# xt60_gh1_25.net
KiCad netlist of a schematic drawn in EasyEDA Pro
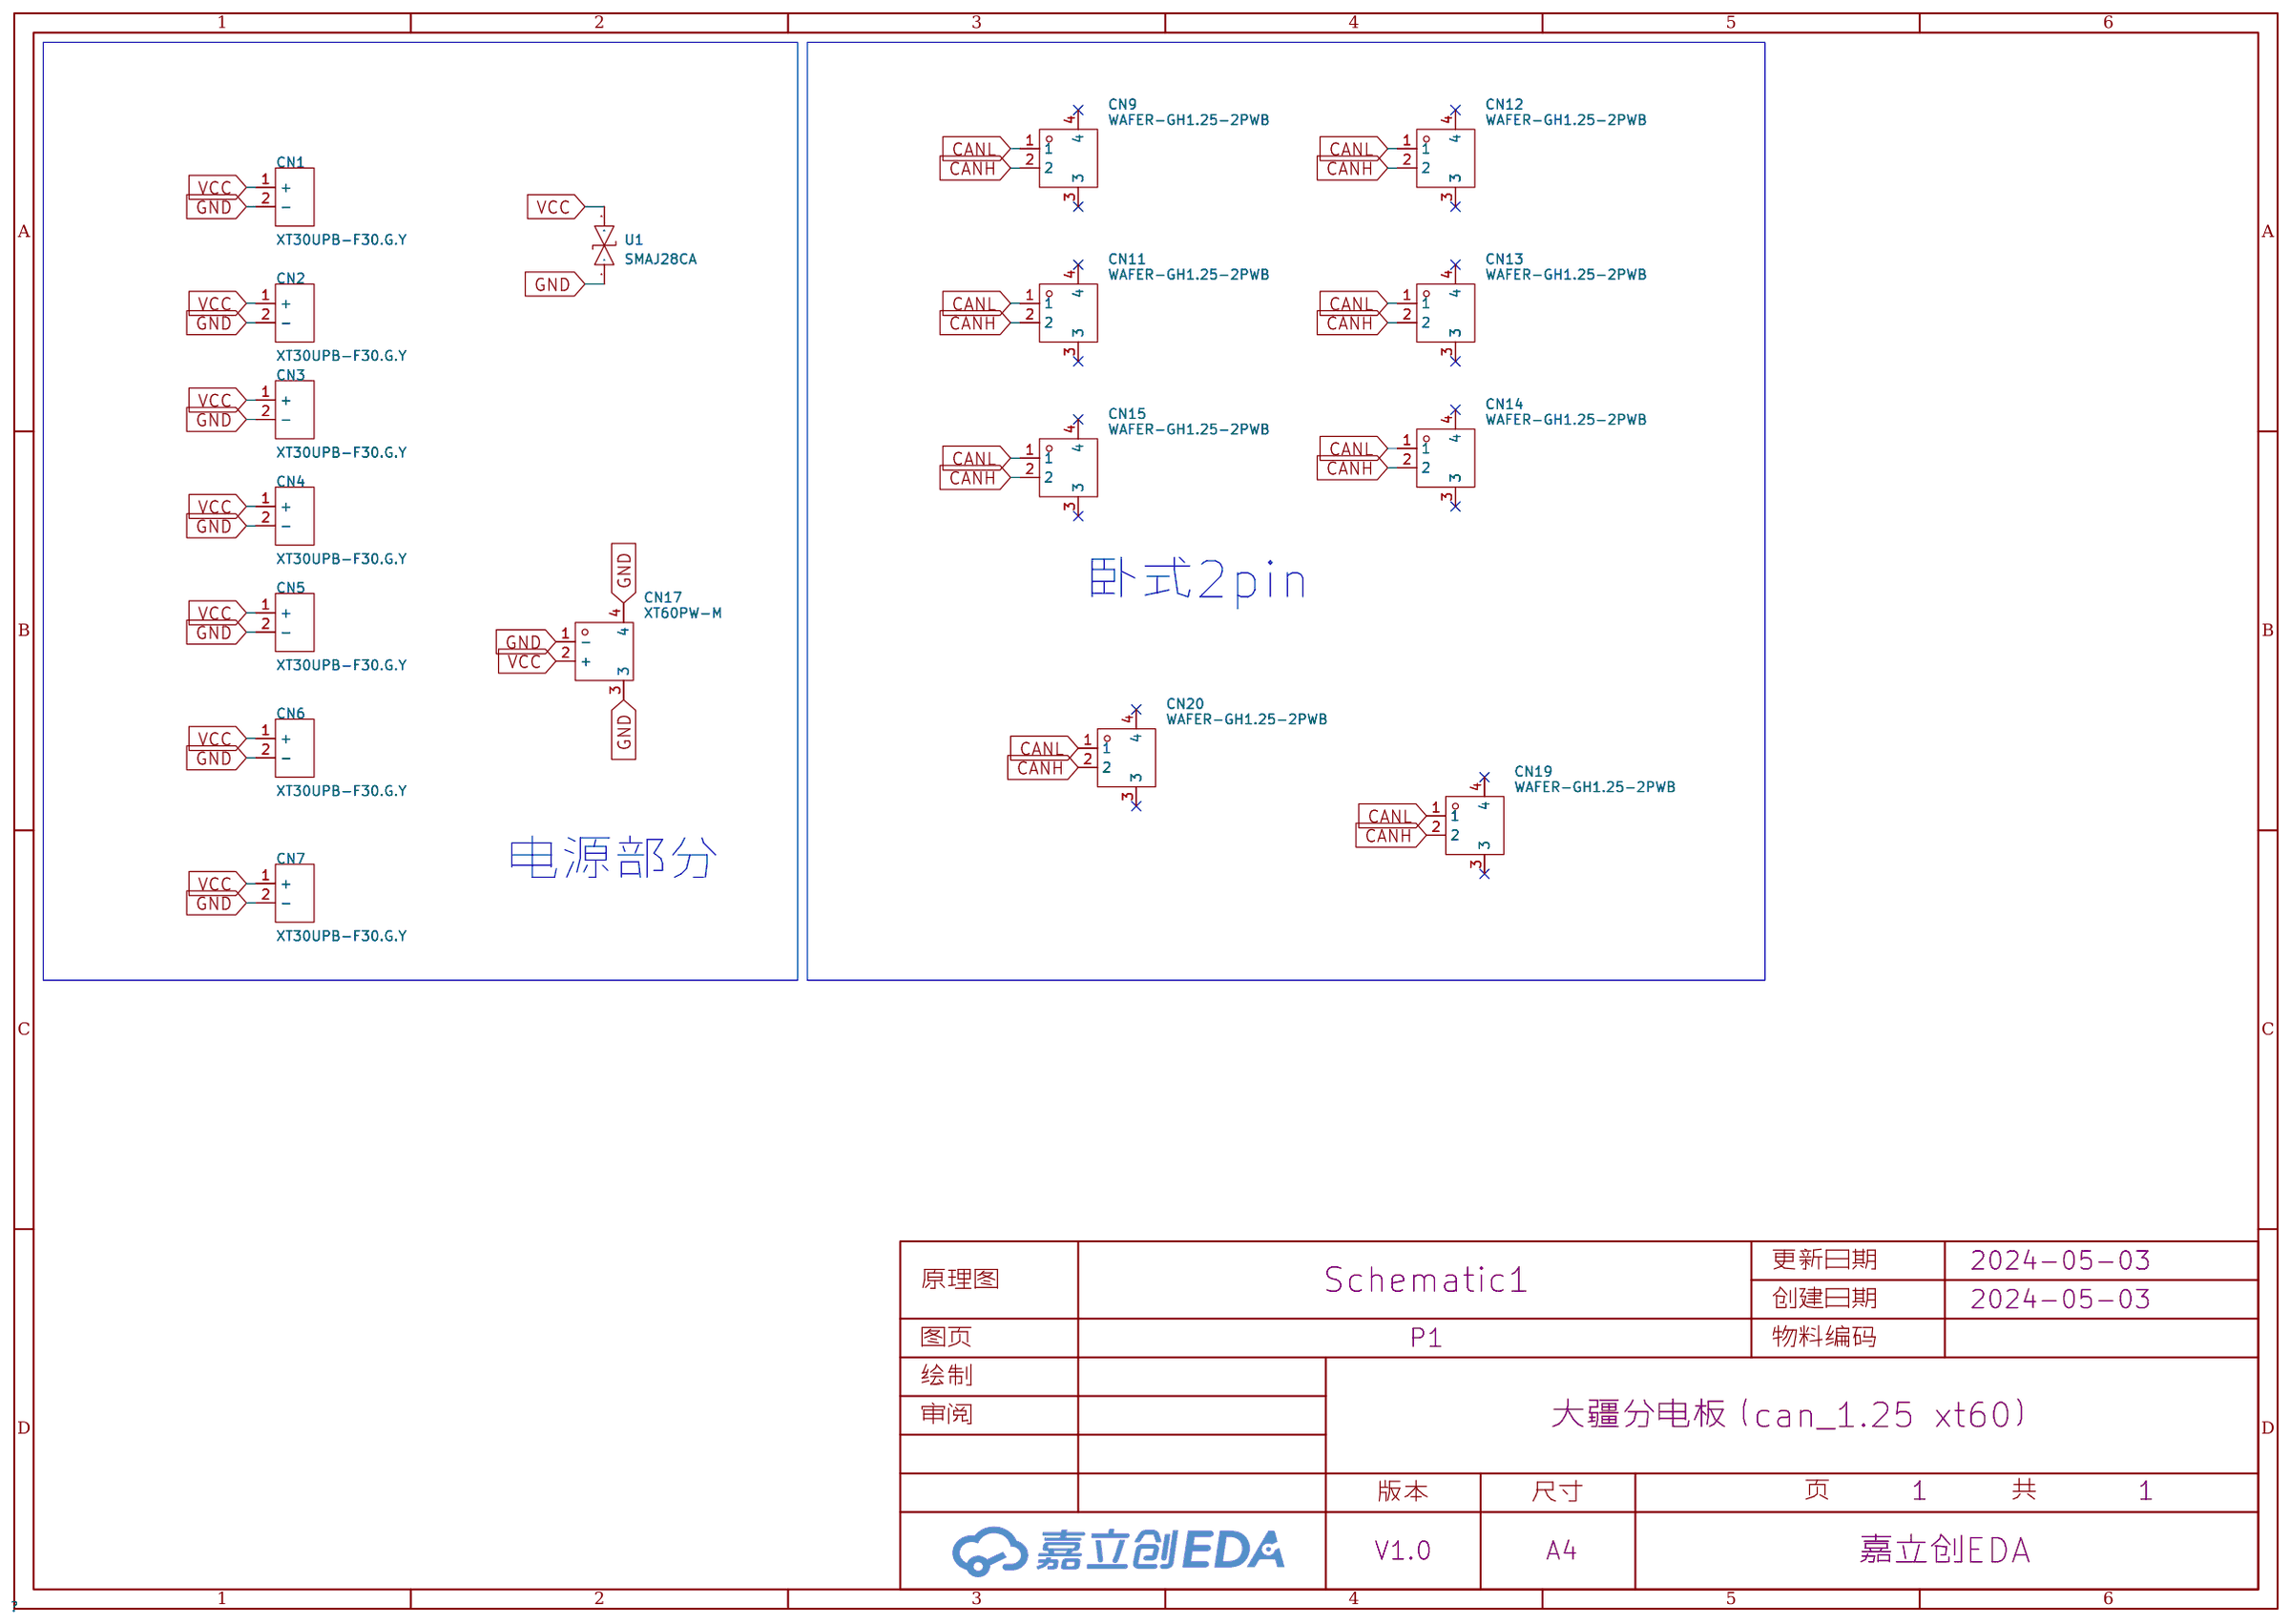
[diagram p0: schematic sheet]

(export (version "E")
  (design (tool "Eeschema 10.0.6"))
  (components
    (comp (ref "CN1")
      (value "XT30UPB-F30.G.Y")
      (footprint "easyedapro:CONN-TH_XT30UPB-F")
      (description "类别:-;类型1:-;")
      (fields (field (name "Manufacturer") "AMASS(艾迈斯)"))
      (libsource (lib "easyedapro") (part "XT30UPB-F"))
    )
    (comp (ref "CN2")
      (value "XT30UPB-F30.G.Y")
      (footprint "easyedapro:CONN-TH_XT30UPB-F")
      (description "类别:-;类型1:-;")
      (fields (field (name "Manufacturer") "AMASS(艾迈斯)"))
      (libsource (lib "easyedapro") (part "XT30UPB-F"))
    )
    (comp (ref "CN3")
      (value "XT30UPB-F30.G.Y")
      (footprint "easyedapro:CONN-TH_XT30UPB-F")
      (description "类别:-;类型1:-;")
      (fields (field (name "Manufacturer") "AMASS(艾迈斯)"))
      (libsource (lib "easyedapro") (part "XT30UPB-F"))
    )
    (comp (ref "CN4")
      (value "XT30UPB-F30.G.Y")
      (footprint "easyedapro:CONN-TH_XT30UPB-F")
      (description "类别:-;类型1:-;")
      (fields (field (name "Manufacturer") "AMASS(艾迈斯)"))
      (libsource (lib "easyedapro") (part "XT30UPB-F"))
    )
    (comp (ref "CN5")
      (value "XT30UPB-F30.G.Y")
      (footprint "easyedapro:CONN-TH_XT30UPB-F")
      (description "类别:-;类型1:-;")
      (fields (field (name "Manufacturer") "AMASS(艾迈斯)"))
      (libsource (lib "easyedapro") (part "XT30UPB-F"))
    )
    (comp (ref "CN6")
      (value "XT30UPB-F30.G.Y")
      (footprint "easyedapro:CONN-TH_XT30UPB-F")
      (description "类别:-;类型1:-;")
      (fields (field (name "Manufacturer") "AMASS(艾迈斯)"))
      (libsource (lib "easyedapro") (part "XT30UPB-F"))
    )
    (comp (ref "CN7")
      (value "XT30UPB-F30.G.Y")
      (footprint "easyedapro:CONN-TH_XT30UPB-F")
      (description "类别:-;类型1:-;")
      (fields (field (name "Manufacturer") "AMASS(艾迈斯)"))
      (libsource (lib "easyedapro") (part "XT30UPB-F"))
    )
    (comp (ref "CN9")
      (value "WAFER-GH1.25-2PWB")
      (footprint "easyedapro:CONN-TH_2P-P1.25_XUNPU_WAFER-GH1.25-2PWB")
      (description "插针结构:1x2P;间距:1.25mm;安装方式:卧贴;参考系列:GH;总PIN数:2P;排数:1;每排PIN数:2;额定电流:1A;工作温度范围:-25°C~+85°C;")
      (fields (field (name "Manufacturer") "XUNPU(讯普)"))
      (libsource (lib "easyedapro") (part "WAFER-GH1.25-2PWB"))
    )
    (comp (ref "CN11")
      (value "WAFER-GH1.25-2PWB")
      (footprint "easyedapro:CONN-TH_2P-P1.25_XUNPU_WAFER-GH1.25-2PWB")
      (description "插针结构:1x2P;间距:1.25mm;安装方式:卧贴;参考系列:GH;总PIN数:2P;排数:1;每排PIN数:2;额定电流:1A;工作温度范围:-25°C~+85°C;")
      (fields (field (name "Manufacturer") "XUNPU(讯普)"))
      (libsource (lib "easyedapro") (part "WAFER-GH1.25-2PWB"))
    )
    (comp (ref "CN12")
      (value "WAFER-GH1.25-2PWB")
      (footprint "easyedapro:CONN-TH_2P-P1.25_XUNPU_WAFER-GH1.25-2PWB")
      (description "插针结构:1x2P;间距:1.25mm;安装方式:卧贴;参考系列:GH;总PIN数:2P;排数:1;每排PIN数:2;额定电流:1A;工作温度范围:-25°C~+85°C;")
      (fields (field (name "Manufacturer") "XUNPU(讯普)"))
      (libsource (lib "easyedapro") (part "WAFER-GH1.25-2PWB"))
    )
    (comp (ref "CN13")
      (value "WAFER-GH1.25-2PWB")
      (footprint "easyedapro:CONN-TH_2P-P1.25_XUNPU_WAFER-GH1.25-2PWB")
      (description "插针结构:1x2P;间距:1.25mm;安装方式:卧贴;参考系列:GH;总PIN数:2P;排数:1;每排PIN数:2;额定电流:1A;工作温度范围:-25°C~+85°C;")
      (fields (field (name "Manufacturer") "XUNPU(讯普)"))
      (libsource (lib "easyedapro") (part "WAFER-GH1.25-2PWB"))
    )
    (comp (ref "CN14")
      (value "WAFER-GH1.25-2PWB")
      (footprint "easyedapro:CONN-TH_2P-P1.25_XUNPU_WAFER-GH1.25-2PWB")
      (description "插针结构:1x2P;间距:1.25mm;安装方式:卧贴;参考系列:GH;总PIN数:2P;排数:1;每排PIN数:2;额定电流:1A;工作温度范围:-25°C~+85°C;")
      (fields (field (name "Manufacturer") "XUNPU(讯普)"))
      (libsource (lib "easyedapro") (part "WAFER-GH1.25-2PWB"))
    )
    (comp (ref "CN15")
      (value "WAFER-GH1.25-2PWB")
      (footprint "easyedapro:CONN-TH_2P-P1.25_XUNPU_WAFER-GH1.25-2PWB")
      (description "插针结构:1x2P;间距:1.25mm;安装方式:卧贴;参考系列:GH;总PIN数:2P;排数:1;每排PIN数:2;额定电流:1A;工作温度范围:-25°C~+85°C;")
      (fields (field (name "Manufacturer") "XUNPU(讯普)"))
      (libsource (lib "easyedapro") (part "WAFER-GH1.25-2PWB"))
    )
    (comp (ref "CN17")
      (value "XT60PW-M")
      (footprint "easyedapro:CONN-TH_XT60PW-M")
      (description "类别:-;类型1:-;")
      (fields (field (name "Manufacturer") "AMASS(艾迈斯)"))
      (libsource (lib "easyedapro") (part "XT60PW-M"))
    )
    (comp (ref "CN19")
      (value "WAFER-GH1.25-2PWB")
      (footprint "easyedapro:CONN-TH_2P-P1.25_XUNPU_WAFER-GH1.25-2PWB")
      (description "插针结构:1x2P;间距:1.25mm;安装方式:卧贴;参考系列:GH;总PIN数:2P;排数:1;每排PIN数:2;额定电流:1A;工作温度范围:-25°C~+85°C;")
      (fields (field (name "Manufacturer") "XUNPU(讯普)"))
      (libsource (lib "easyedapro") (part "WAFER-GH1.25-2PWB"))
    )
    (comp (ref "CN20")
      (value "WAFER-GH1.25-2PWB")
      (footprint "easyedapro:CONN-TH_2P-P1.25_XUNPU_WAFER-GH1.25-2PWB")
      (description "插针结构:1x2P;间距:1.25mm;安装方式:卧贴;参考系列:GH;总PIN数:2P;排数:1;每排PIN数:2;额定电流:1A;工作温度范围:-25°C~+85°C;")
      (fields (field (name "Manufacturer") "XUNPU(讯普)"))
      (libsource (lib "easyedapro") (part "WAFER-GH1.25-2PWB"))
    )
    (comp (ref "U1")
      (value "SMAJ28CA")
      (footprint "easyedapro:SMA_L4.3-W2.7-LS5.0-BI")
      (description "反向截止电压(Vrwm):28V;最大钳位电压:45.4V;峰值脉冲电流(Ipp)@10/1000us:8.8A;击穿电压:31.1V;")
      (fields (field (name "Manufacturer") "GOODWORK(固得沃克)"))
      (libsource (lib "easyedapro") (part "SMAJ28CA_C908827"))
    )
  )
  (nets
    (net (code "1") (name "CANH") (class "Default")
      (node (ref "CN11") (pin "2") (pinfunction "2_2") (pintype "unspecified"))
      (node (ref "CN12") (pin "2") (pinfunction "2_2") (pintype "unspecified"))
      (node (ref "CN13") (pin "2") (pinfunction "2_2") (pintype "unspecified"))
      (node (ref "CN14") (pin "2") (pinfunction "2_2") (pintype "unspecified"))
      (node (ref "CN15") (pin "2") (pinfunction "2_2") (pintype "unspecified"))
      (node (ref "CN19") (pin "2") (pinfunction "2_2") (pintype "unspecified"))
      (node (ref "CN20") (pin "2") (pinfunction "2_2") (pintype "unspecified"))
      (node (ref "CN9") (pin "2") (pinfunction "2_2") (pintype "unspecified"))
    )
    (net (code "2") (name "CANL") (class "Default")
      (node (ref "CN11") (pin "1") (pinfunction "1_1") (pintype "unspecified"))
      (node (ref "CN12") (pin "1") (pinfunction "1_1") (pintype "unspecified"))
      (node (ref "CN13") (pin "1") (pinfunction "1_1") (pintype "unspecified"))
      (node (ref "CN14") (pin "1") (pinfunction "1_1") (pintype "unspecified"))
      (node (ref "CN15") (pin "1") (pinfunction "1_1") (pintype "unspecified"))
      (node (ref "CN19") (pin "1") (pinfunction "1_1") (pintype "unspecified"))
      (node (ref "CN20") (pin "1") (pinfunction "1_1") (pintype "unspecified"))
      (node (ref "CN9") (pin "1") (pinfunction "1_1") (pintype "unspecified"))
    )
    (net (code "3") (name "GND") (class "Default")
      (node (ref "CN1") (pin "2") (pinfunction "-_2") (pintype "unspecified"))
      (node (ref "CN17") (pin "1") (pinfunction "-_1") (pintype "unspecified"))
      (node (ref "CN17") (pin "3") (pinfunction "3_3") (pintype "unspecified"))
      (node (ref "CN17") (pin "4") (pinfunction "4_4") (pintype "unspecified"))
      (node (ref "CN2") (pin "2") (pinfunction "-_2") (pintype "unspecified"))
      (node (ref "CN3") (pin "2") (pinfunction "-_2") (pintype "unspecified"))
      (node (ref "CN4") (pin "2") (pinfunction "-_2") (pintype "unspecified"))
      (node (ref "CN5") (pin "2") (pinfunction "-_2") (pintype "unspecified"))
      (node (ref "CN6") (pin "2") (pinfunction "-_2") (pintype "unspecified"))
      (node (ref "CN7") (pin "2") (pinfunction "-_2") (pintype "unspecified"))
      (node (ref "U1") (pin "1") (pinfunction "1_1") (pintype "unspecified"))
    )
    (net (code "4") (name "VCC") (class "Default")
      (node (ref "CN1") (pin "1") (pinfunction "+_1") (pintype "unspecified"))
      (node (ref "CN17") (pin "2") (pinfunction "+_2") (pintype "unspecified"))
      (node (ref "CN2") (pin "1") (pinfunction "+_1") (pintype "unspecified"))
      (node (ref "CN3") (pin "1") (pinfunction "+_1") (pintype "unspecified"))
      (node (ref "CN4") (pin "1") (pinfunction "+_1") (pintype "unspecified"))
      (node (ref "CN5") (pin "1") (pinfunction "+_1") (pintype "unspecified"))
      (node (ref "CN6") (pin "1") (pinfunction "+_1") (pintype "unspecified"))
      (node (ref "CN7") (pin "1") (pinfunction "+_1") (pintype "unspecified"))
      (node (ref "U1") (pin "2") (pinfunction "2_2") (pintype "unspecified"))
    )
    (net (code "5") (name "unconnected-(CN9-Pad3)") (class "Default")
      (node (ref "CN9") (pin "3") (pinfunction "3_3") (pintype "unspecified+no_connect"))
    )
    (net (code "6") (name "unconnected-(CN9-Pad4)") (class "Default")
      (node (ref "CN9") (pin "4") (pinfunction "4_4") (pintype "unspecified+no_connect"))
    )
    (net (code "7") (name "unconnected-(CN11-Pad3)") (class "Default")
      (node (ref "CN11") (pin "3") (pinfunction "3_3") (pintype "unspecified+no_connect"))
    )
    (net (code "8") (name "unconnected-(CN11-Pad4)") (class "Default")
      (node (ref "CN11") (pin "4") (pinfunction "4_4") (pintype "unspecified+no_connect"))
    )
    (net (code "9") (name "unconnected-(CN12-Pad3)") (class "Default")
      (node (ref "CN12") (pin "3") (pinfunction "3_3") (pintype "unspecified+no_connect"))
    )
    (net (code "10") (name "unconnected-(CN12-Pad4)") (class "Default")
      (node (ref "CN12") (pin "4") (pinfunction "4_4") (pintype "unspecified+no_connect"))
    )
    (net (code "11") (name "unconnected-(CN13-Pad3)") (class "Default")
      (node (ref "CN13") (pin "3") (pinfunction "3_3") (pintype "unspecified+no_connect"))
    )
    (net (code "12") (name "unconnected-(CN13-Pad4)") (class "Default")
      (node (ref "CN13") (pin "4") (pinfunction "4_4") (pintype "unspecified+no_connect"))
    )
    (net (code "13") (name "unconnected-(CN14-Pad3)") (class "Default")
      (node (ref "CN14") (pin "3") (pinfunction "3_3") (pintype "unspecified+no_connect"))
    )
    (net (code "14") (name "unconnected-(CN14-Pad4)") (class "Default")
      (node (ref "CN14") (pin "4") (pinfunction "4_4") (pintype "unspecified+no_connect"))
    )
    (net (code "15") (name "unconnected-(CN15-Pad3)") (class "Default")
      (node (ref "CN15") (pin "3") (pinfunction "3_3") (pintype "unspecified+no_connect"))
    )
    (net (code "16") (name "unconnected-(CN15-Pad4)") (class "Default")
      (node (ref "CN15") (pin "4") (pinfunction "4_4") (pintype "unspecified+no_connect"))
    )
    (net (code "17") (name "unconnected-(CN19-Pad3)") (class "Default")
      (node (ref "CN19") (pin "3") (pinfunction "3_3") (pintype "unspecified+no_connect"))
    )
    (net (code "18") (name "unconnected-(CN19-Pad4)") (class "Default")
      (node (ref "CN19") (pin "4") (pinfunction "4_4") (pintype "unspecified+no_connect"))
    )
    (net (code "19") (name "unconnected-(CN20-Pad3)") (class "Default")
      (node (ref "CN20") (pin "3") (pinfunction "3_3") (pintype "unspecified+no_connect"))
    )
    (net (code "20") (name "unconnected-(CN20-Pad4)") (class "Default")
      (node (ref "CN20") (pin "4") (pinfunction "4_4") (pintype "unspecified+no_connect"))
    )
  )
)
